# Set-Mile-TOP.net
KiCad netlist of a schematic drawn in EAGLE
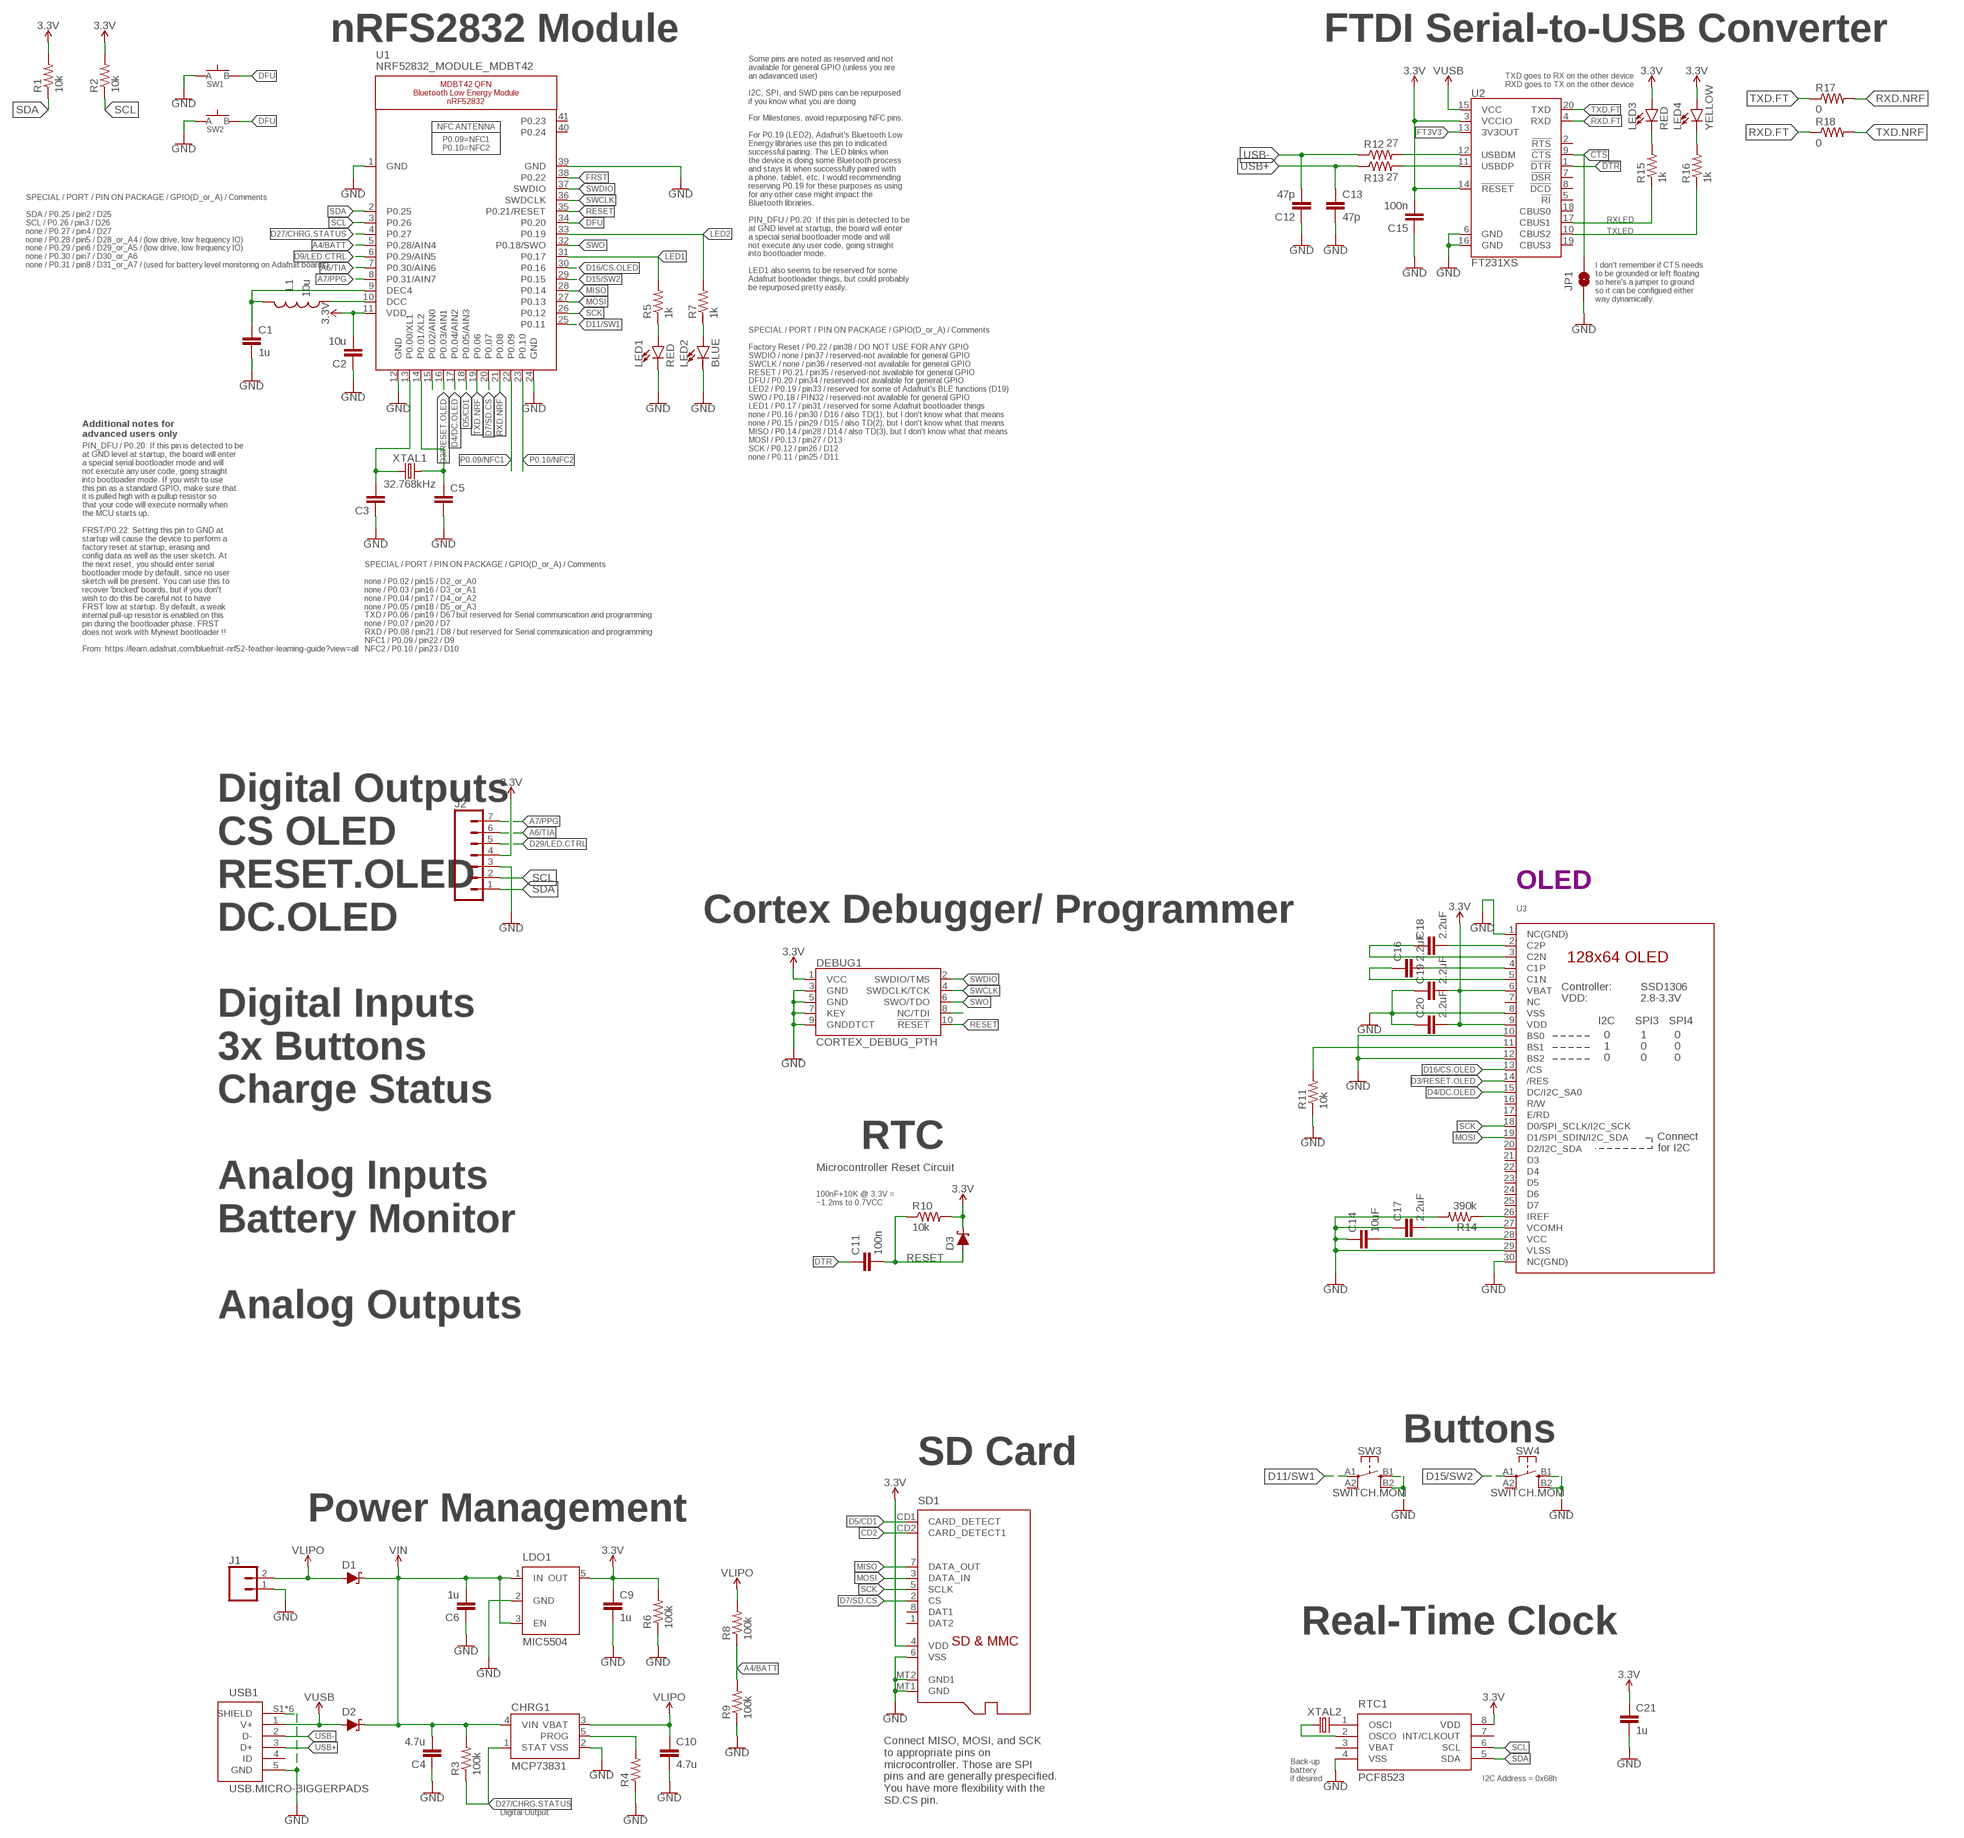
[diagram p0: schematic, sheet 1]

(export (version "E")
  (design (tool "Eeschema 10.0.6"))
  (components
    (comp (ref "C1")
      (value "1u")
      (footprint "eagle-import:C0603")
      (libsource (lib "eagle-import") (part "CAPACITOR0603"))
    )
    (comp (ref "C2")
      (value "10u")
      (footprint "eagle-import:C0805")
      (libsource (lib "eagle-import") (part "CAPACITOR0805"))
    )
    (comp (ref "C3")
      (value "CAPACITOR0603")
      (footprint "eagle-import:C0603")
      (libsource (lib "eagle-import") (part "CAPACITOR0603"))
    )
    (comp (ref "C4")
      (value "4.7u")
      (footprint "eagle-import:C0603")
      (libsource (lib "eagle-import") (part "CAPACITOR0603"))
    )
    (comp (ref "C5")
      (value "CAPACITOR0603")
      (footprint "eagle-import:C0603")
      (libsource (lib "eagle-import") (part "CAPACITOR0603"))
    )
    (comp (ref "C6")
      (value "1u")
      (footprint "eagle-import:C0603")
      (libsource (lib "eagle-import") (part "CAPACITOR0603"))
    )
    (comp (ref "C9")
      (value "1u")
      (footprint "eagle-import:C0603")
      (libsource (lib "eagle-import") (part "CAPACITOR0603"))
    )
    (comp (ref "C10")
      (value "4.7u")
      (footprint "eagle-import:C0603")
      (libsource (lib "eagle-import") (part "CAPACITOR0603"))
    )
    (comp (ref "C11")
      (value "100n")
      (footprint "eagle-import:C0603")
      (libsource (lib "eagle-import") (part "CAPACITOR0603"))
    )
    (comp (ref "C12")
      (value "47p")
      (footprint "eagle-import:C0603")
      (libsource (lib "eagle-import") (part "CAPACITOR0603"))
    )
    (comp (ref "C13")
      (value "47p")
      (footprint "eagle-import:C0603")
      (libsource (lib "eagle-import") (part "CAPACITOR0603"))
    )
    (comp (ref "C14")
      (value "10uF")
      (footprint "eagle-import:C0603")
      (libsource (lib "eagle-import") (part "CAPACITOR0603"))
    )
    (comp (ref "C15")
      (value "100n")
      (footprint "eagle-import:C0603")
      (libsource (lib "eagle-import") (part "CAPACITOR0603"))
    )
    (comp (ref "C16")
      (value "2.2uF")
      (footprint "eagle-import:C0402")
      (libsource (lib "eagle-import") (part "CAPACITOR0402"))
    )
    (comp (ref "C17")
      (value "2.2uF")
      (footprint "eagle-import:C0402")
      (libsource (lib "eagle-import") (part "CAPACITOR0402"))
    )
    (comp (ref "C18")
      (value "2.2uF")
      (footprint "eagle-import:C0402")
      (libsource (lib "eagle-import") (part "CAPACITOR0402"))
    )
    (comp (ref "C19")
      (value "2.2uF")
      (footprint "eagle-import:C0402")
      (libsource (lib "eagle-import") (part "CAPACITOR0402"))
    )
    (comp (ref "C20")
      (value "2.2uF")
      (footprint "eagle-import:C0402")
      (libsource (lib "eagle-import") (part "CAPACITOR0402"))
    )
    (comp (ref "C21")
      (value "1u")
      (footprint "eagle-import:C0603")
      (libsource (lib "eagle-import") (part "CAPACITOR0603"))
    )
    (comp (ref "CHRG1")
      (value "MCP73831")
      (footprint "eagle-import:SOT23-5")
      (libsource (lib "eagle-import") (part "MCP73831"))
    )
    (comp (ref "D1")
      (value "SCHOTTKY-USC")
      (footprint "eagle-import:USC")
      (libsource (lib "eagle-import") (part "SCHOTTKY-USC"))
    )
    (comp (ref "D2")
      (value "SCHOTTKY-USC")
      (footprint "eagle-import:USC")
      (libsource (lib "eagle-import") (part "SCHOTTKY-USC"))
    )
    (comp (ref "D3")
      (value "SCHOTTKY-USC")
      (footprint "eagle-import:USC")
      (libsource (lib "eagle-import") (part "SCHOTTKY-USC"))
    )
    (comp (ref "DEBUG1")
      (value "CORTEX_DEBUG_PTH")
      (footprint "eagle-import:2X5-PTH-1.27MM")
      (libsource (lib "eagle-import") (part "CORTEX_DEBUG_PTH"))
    )
    (comp (ref "J1")
      (value "CONN_02")
      (footprint "eagle-import:1X02")
      (libsource (lib "eagle-import") (part "CONN_02"))
    )
    (comp (ref "J2")
      (value "CONN_07-1.27MM")
      (footprint "eagle-import:1X07_1.27MM")
      (libsource (lib "eagle-import") (part "CONN_07-1.27MM"))
    )
    (comp (ref "JP1")
      (value "JUMPER-SMT_2_NO_SILK")
      (footprint "eagle-import:SMT-JUMPER_2_NO_SILK")
      (libsource (lib "eagle-import") (part "JUMPER-SMT_2_NO_SILK"))
    )
    (comp (ref "L1")
      (value "10u")
      (footprint "eagle-import:L0603")
      (libsource (lib "eagle-import") (part "INDUCTOR0603"))
    )
    (comp (ref "LDO1")
      (value "MIC5504")
      (footprint "eagle-import:SOT23-5")
      (libsource (lib "eagle-import") (part "MIC5504"))
    )
    (comp (ref "LED1")
      (value "RED")
      (footprint "eagle-import:LED-0603")
      (libsource (lib "eagle-import") (part "LED0603"))
    )
    (comp (ref "LED2")
      (value "BLUE")
      (footprint "eagle-import:LED-0603")
      (libsource (lib "eagle-import") (part "LED0603"))
    )
    (comp (ref "LED3")
      (value "RED")
      (footprint "eagle-import:LED-0603")
      (libsource (lib "eagle-import") (part "LED0603"))
    )
    (comp (ref "LED4")
      (value "YELLOW")
      (footprint "eagle-import:LED-0603")
      (libsource (lib "eagle-import") (part "LED0603"))
    )
    (comp (ref "R1")
      (value "10k")
      (footprint "eagle-import:R0603")
      (libsource (lib "eagle-import") (part "RESISTOR0603"))
    )
    (comp (ref "R2")
      (value "10k")
      (footprint "eagle-import:R0603")
      (libsource (lib "eagle-import") (part "RESISTOR0603"))
    )
    (comp (ref "R3")
      (value "100k")
      (footprint "eagle-import:R0603")
      (libsource (lib "eagle-import") (part "RESISTOR0603"))
    )
    (comp (ref "R4")
      (value "RESISTOR0603")
      (footprint "eagle-import:R0603")
      (libsource (lib "eagle-import") (part "RESISTOR0603"))
    )
    (comp (ref "R5")
      (value "1k")
      (footprint "eagle-import:R0603")
      (libsource (lib "eagle-import") (part "RESISTOR0603"))
    )
    (comp (ref "R6")
      (value "100k")
      (footprint "eagle-import:R0603")
      (libsource (lib "eagle-import") (part "RESISTOR0603"))
    )
    (comp (ref "R7")
      (value "1k")
      (footprint "eagle-import:R0603")
      (libsource (lib "eagle-import") (part "RESISTOR0603"))
    )
    (comp (ref "R8")
      (value "100k")
      (footprint "eagle-import:R0603")
      (libsource (lib "eagle-import") (part "RESISTOR0603"))
    )
    (comp (ref "R9")
      (value "100k")
      (footprint "eagle-import:R0603")
      (libsource (lib "eagle-import") (part "RESISTOR0603"))
    )
    (comp (ref "R10")
      (value "10k")
      (footprint "eagle-import:R0603")
      (libsource (lib "eagle-import") (part "RESISTOR0603"))
    )
    (comp (ref "R11")
      (value "10k")
      (footprint "eagle-import:R0603")
      (libsource (lib "eagle-import") (part "RESISTOR0603"))
    )
    (comp (ref "R12")
      (value "27")
      (footprint "eagle-import:R0603")
      (libsource (lib "eagle-import") (part "RESISTOR0603"))
    )
    (comp (ref "R13")
      (value "27")
      (footprint "eagle-import:R0603")
      (libsource (lib "eagle-import") (part "RESISTOR0603"))
    )
    (comp (ref "R14")
      (value "390k")
      (footprint "eagle-import:R0603")
      (libsource (lib "eagle-import") (part "RESISTOR0603"))
    )
    (comp (ref "R15")
      (value "1k")
      (footprint "eagle-import:R0603")
      (libsource (lib "eagle-import") (part "RESISTOR0603"))
    )
    (comp (ref "R16")
      (value "1k")
      (footprint "eagle-import:R0603")
      (libsource (lib "eagle-import") (part "RESISTOR0603"))
    )
    (comp (ref "R17")
      (value "0")
      (footprint "eagle-import:R0603")
      (libsource (lib "eagle-import") (part "RESISTOR0603"))
    )
    (comp (ref "R18")
      (value "0")
      (footprint "eagle-import:R0603")
      (libsource (lib "eagle-import") (part "RESISTOR0603"))
    )
    (comp (ref "RTC1")
      (value "PCF8523")
      (footprint "eagle-import:SO8")
      (libsource (lib "eagle-import") (part "PCF8523"))
    )
    (comp (ref "SD1")
      (value "MICROSD")
      (footprint "eagle-import:MICROSD")
      (libsource (lib "eagle-import") (part "MICROSD"))
    )
    (comp (ref "SW1")
      (value "SPST-PTS830GG140-COPY.1-3")
      (footprint "eagle-import:BUTTON-GULLWING")
      (libsource (lib "eagle-import") (part "SPST-PTS830GG140-COPY.1-3"))
    )
    (comp (ref "SW2")
      (value "SPST-PTS830GG140-COPY.1-3")
      (footprint "eagle-import:BUTTON-GULLWING")
      (libsource (lib "eagle-import") (part "SPST-PTS830GG140-COPY.1-3"))
    )
    (comp (ref "SW3")
      (value "SWITCH.MOM")
      (footprint "eagle-import:TACTILE_SWITCH_SMD_6.2MM_TALL")
      (libsource (lib "eagle-import") (part "SWITCH.MOM"))
    )
    (comp (ref "SW4")
      (value "SWITCH.MOM")
      (footprint "eagle-import:TACTILE_SWITCH_SMD_6.2MM_TALL")
      (libsource (lib "eagle-import") (part "SWITCH.MOM"))
    )
    (comp (ref "U1")
      (value "NRF52832_MODULE_MDBT42")
      (footprint "eagle-import:BLE_MODULE_RAYTAC_MDBT42")
      (libsource (lib "eagle-import") (part "NRF52832_MODULE_MDBT42"))
    )
    (comp (ref "U2")
      (value "FT231XS")
      (footprint "eagle-import:SSOP20_L")
      (libsource (lib "eagle-import") (part "FT231XS"))
    )
    (comp (ref "U3")
      (value "DISP_OLED_UG-2864HSWEG01-NO-WRAPAROUND")
      (footprint "eagle-import:UG-2864HSWEG01_0.96IN_NO-WRAPAROUND")
      (libsource (lib "eagle-import") (part "DISP_OLED_UG-2864HSWEG01-NO-WRAPAROUND"))
    )
    (comp (ref "USB1")
      (value "USB.MICRO-BIGGERPADS")
      (footprint "eagle-import:USB-MICRO-01.BIGGERPADS")
      (libsource (lib "eagle-import") (part "USB.MICRO-BIGGERPADS"))
    )
    (comp (ref "XTAL1")
      (value "32.768kHz")
      (footprint "eagle-import:2-SMD.NOLEAD.2.0MMTO1.2MM")
      (libsource (lib "eagle-import") (part "CRYSTALECS-.327-12.5-12-C-TR"))
    )
    (comp (ref "XTAL2")
      (value "32.7680kHz")
      (footprint "eagle-import:2-SMD.NOLEAD.2.0MMTO1.2MM")
      (libsource (lib "eagle-import") (part "CRYSTALECS-.327-12.5-12-C-TR"))
    )
  )
  (nets
    (net (code "1") (name "/RXLED") (class "Default")
      (node (ref "R15") (pin "1") (pinfunction "1_1") (pintype "passive"))
      (node (ref "U2") (pin "17") (pinfunction "CBUS1_17") (pintype "bidirectional"))
    )
    (net (code "2") (name "/TXLED") (class "Default")
      (node (ref "R16") (pin "1") (pinfunction "1_1") (pintype "passive"))
      (node (ref "U2") (pin "10") (pinfunction "CBUS2_10") (pintype "bidirectional"))
    )
    (net (code "3") (name "/~{CTS}") (class "Default")
      (node (ref "JP1") (pin "2") (pinfunction "2_2") (pintype "passive"))
      (node (ref "U2") (pin "9") (pinfunction "~{CTS}_9") (pintype "bidirectional"))
    )
    (net (code "4") (name "/~{DTR}") (class "Default")
      (node (ref "U2") (pin "1") (pinfunction "~{DTR}_1") (pintype "bidirectional"))
    )
    (net (code "5") (name "3.3V") (class "Default")
      (node (ref "C15") (pin "2") (pinfunction "2_2") (pintype "passive"))
      (node (ref "C19") (pin "2") (pinfunction "2_2") (pintype "passive"))
      (node (ref "C2") (pin "2") (pinfunction "2_2") (pintype "passive"))
      (node (ref "C20") (pin "2") (pinfunction "2_2") (pintype "passive"))
      (node (ref "C21") (pin "1") (pinfunction "1_1") (pintype "passive"))
      (node (ref "C9") (pin "1") (pinfunction "1_1") (pintype "passive"))
      (node (ref "D3") (pin "-") (pinfunction "C_-") (pintype "passive"))
      (node (ref "DEBUG1") (pin "1") (pinfunction "VCC_1") (pintype "bidirectional"))
      (node (ref "J2") (pin "4") (pinfunction "4_4") (pintype "passive"))
      (node (ref "LDO1") (pin "5") (pinfunction "OUT_5") (pintype "bidirectional"))
      (node (ref "LED3") (pin "A") (pinfunction "A_A") (pintype "passive"))
      (node (ref "LED4") (pin "A") (pinfunction "A_A") (pintype "passive"))
      (node (ref "R1") (pin "2") (pinfunction "2_2") (pintype "passive"))
      (node (ref "R10") (pin "2") (pinfunction "2_2") (pintype "passive"))
      (node (ref "R2") (pin "2") (pinfunction "2_2") (pintype "passive"))
      (node (ref "R6") (pin "2") (pinfunction "2_2") (pintype "passive"))
      (node (ref "RTC1") (pin "8") (pinfunction "VDD_8") (pintype "bidirectional"))
      (node (ref "SD1") (pin "4") (pinfunction "VDD_4") (pintype "power_in"))
      (node (ref "U1") (pin "11") (pinfunction "VDD_11") (pintype "bidirectional"))
      (node (ref "U2") (pin "14") (pinfunction "~{RESET}_14") (pintype "bidirectional"))
      (node (ref "U2") (pin "3") (pinfunction "VCCIO_3") (pintype "bidirectional"))
      (node (ref "U3") (pin "6") (pinfunction "VBAT_6") (pintype "input"))
      (node (ref "U3") (pin "9") (pinfunction "VDD_9") (pintype "power_in"))
    )
    (net (code "6") (name "A4{slash}BATT") (class "Default")
      (node (ref "R8") (pin "1") (pinfunction "1_1") (pintype "passive"))
      (node (ref "R9") (pin "2") (pinfunction "2_2") (pintype "passive"))
      (node (ref "U1") (pin "5") (pinfunction "P0.28/AIN4_5") (pintype "bidirectional"))
    )
    (net (code "7") (name "A6{slash}TIA") (class "Default")
      (node (ref "J2") (pin "6") (pinfunction "6_6") (pintype "passive"))
      (node (ref "U1") (pin "7") (pinfunction "P0.30/AIN6_7") (pintype "bidirectional"))
    )
    (net (code "8") (name "A7{slash}PPG") (class "Default")
      (node (ref "J2") (pin "7") (pinfunction "7_7") (pintype "passive"))
      (node (ref "U1") (pin "8") (pinfunction "P0.31/AIN7_8") (pintype "bidirectional"))
    )
    (net (code "9") (name "CD2") (class "Default")
      (node (ref "SD1") (pin "CD2") (pinfunction "CARD_DETECT1_CD2") (pintype "passive"))
    )
    (net (code "10") (name "D3{slash}RESET.OLED") (class "Default")
      (node (ref "U1") (pin "16") (pinfunction "P0.03/AIN1_16") (pintype "bidirectional"))
      (node (ref "U3") (pin "14") (pinfunction "/RES_14") (pintype "input"))
    )
    (net (code "11") (name "D4{slash}DC.OLED") (class "Default")
      (node (ref "U1") (pin "15") (pinfunction "P0.02/AIN0_15") (pintype "bidirectional"))
      (node (ref "U1") (pin "17") (pinfunction "P0.04/AIN2_17") (pintype "bidirectional"))
      (node (ref "U3") (pin "15") (pinfunction "DC/I2C_SA0_15") (pintype "input"))
    )
    (net (code "12") (name "D5{slash}CD1") (class "Default")
      (node (ref "SD1") (pin "CD1") (pinfunction "CARD_DETECT_CD1") (pintype "passive"))
      (node (ref "U1") (pin "18") (pinfunction "P0.05/AIN3_18") (pintype "bidirectional"))
    )
    (net (code "13") (name "D7{slash}SD.CS") (class "Default")
      (node (ref "SD1") (pin "2") (pinfunction "CS_2") (pintype "input"))
      (node (ref "U1") (pin "20") (pinfunction "P0.07_20") (pintype "bidirectional"))
    )
    (net (code "14") (name "D9{slash}LED.CTRL") (class "Default")
      (node (ref "U1") (pin "6") (pinfunction "P0.29/AIN5_6") (pintype "bidirectional"))
    )
    (net (code "15") (name "D11{slash}SW1") (class "Default")
      (node (ref "SW3") (pin "A1") (pinfunction "1_A1") (pintype "passive"))
      (node (ref "U1") (pin "25") (pinfunction "P0.11_25") (pintype "bidirectional"))
    )
    (net (code "16") (name "D15{slash}SW2") (class "Default")
      (node (ref "SW4") (pin "A1") (pinfunction "1_A1") (pintype "passive"))
      (node (ref "U1") (pin "29") (pinfunction "P0.15_29") (pintype "bidirectional"))
    )
    (net (code "17") (name "D16{slash}CS.OLED") (class "Default")
      (node (ref "U1") (pin "30") (pinfunction "P0.16_30") (pintype "bidirectional"))
      (node (ref "U3") (pin "13") (pinfunction "/CS_13") (pintype "input"))
    )
    (net (code "18") (name "D27{slash}CHRG.STATUS") (class "Default")
      (node (ref "CHRG1") (pin "1") (pinfunction "STAT_1") (pintype "output"))
      (node (ref "R3") (pin "1") (pinfunction "1_1") (pintype "passive"))
      (node (ref "U1") (pin "4") (pinfunction "P0.27_4") (pintype "bidirectional"))
    )
    (net (code "19") (name "D29{slash}LED.CTRL") (class "Default")
      (node (ref "J2") (pin "5") (pinfunction "5_5") (pintype "passive"))
    )
    (net (code "20") (name "DFU") (class "Default")
      (node (ref "SW1") (pin "3") (pinfunction "B_3") (pintype "bidirectional"))
      (node (ref "SW2") (pin "3") (pinfunction "B_3") (pintype "bidirectional"))
      (node (ref "U1") (pin "34") (pinfunction "P0.20_34") (pintype "bidirectional"))
    )
    (net (code "21") (name "DTR") (class "Default")
      (node (ref "C11") (pin "1") (pinfunction "1_1") (pintype "passive"))
    )
    (net (code "22") (name "FRST") (class "Default")
      (node (ref "U1") (pin "38") (pinfunction "P0.22_38") (pintype "bidirectional"))
    )
    (net (code "23") (name "FT3V3") (class "Default")
      (node (ref "U2") (pin "13") (pinfunction "3V3OUT_13") (pintype "bidirectional"))
    )
    (net (code "24") (name "GND") (class "Default")
      (node (ref "C1") (pin "2") (pinfunction "2_2") (pintype "passive"))
      (node (ref "C10") (pin "2") (pinfunction "2_2") (pintype "passive"))
      (node (ref "C12") (pin "1") (pinfunction "1_1") (pintype "passive"))
      (node (ref "C13") (pin "2") (pinfunction "2_2") (pintype "passive"))
      (node (ref "C14") (pin "1") (pinfunction "1_1") (pintype "passive"))
      (node (ref "C15") (pin "1") (pinfunction "1_1") (pintype "passive"))
      (node (ref "C17") (pin "1") (pinfunction "1_1") (pintype "passive"))
      (node (ref "C19") (pin "1") (pinfunction "1_1") (pintype "passive"))
      (node (ref "C2") (pin "1") (pinfunction "1_1") (pintype "passive"))
      (node (ref "C20") (pin "1") (pinfunction "1_1") (pintype "passive"))
      (node (ref "C21") (pin "2") (pinfunction "2_2") (pintype "passive"))
      (node (ref "C3") (pin "1") (pinfunction "1_1") (pintype "passive"))
      (node (ref "C4") (pin "1") (pinfunction "1_1") (pintype "passive"))
      (node (ref "C5") (pin "2") (pinfunction "2_2") (pintype "passive"))
      (node (ref "C6") (pin "1") (pinfunction "1_1") (pintype "passive"))
      (node (ref "C9") (pin "2") (pinfunction "2_2") (pintype "passive"))
      (node (ref "CHRG1") (pin "2") (pinfunction "VSS_2") (pintype "power_in"))
      (node (ref "DEBUG1") (pin "3") (pinfunction "GND_3") (pintype "bidirectional"))
      (node (ref "DEBUG1") (pin "5") (pinfunction "GND_5") (pintype "bidirectional"))
      (node (ref "DEBUG1") (pin "7") (pinfunction "KEY_7") (pintype "bidirectional"))
      (node (ref "DEBUG1") (pin "9") (pinfunction "GNDDTCT_9") (pintype "bidirectional"))
      (node (ref "J1") (pin "1") (pinfunction "1_1") (pintype "passive"))
      (node (ref "J2") (pin "3") (pinfunction "3_3") (pintype "passive"))
      (node (ref "JP1") (pin "1") (pinfunction "1_1") (pintype "passive"))
      (node (ref "LDO1") (pin "2") (pinfunction "GND_2") (pintype "bidirectional"))
      (node (ref "LED1") (pin "C") (pinfunction "C_C") (pintype "passive"))
      (node (ref "LED2") (pin "C") (pinfunction "C_C") (pintype "passive"))
      (node (ref "R11") (pin "1") (pinfunction "1_1") (pintype "passive"))
      (node (ref "R14") (pin "2") (pinfunction "2_2") (pintype "passive"))
      (node (ref "R4") (pin "1") (pinfunction "1_1") (pintype "passive"))
      (node (ref "R6") (pin "1") (pinfunction "1_1") (pintype "passive"))
      (node (ref "R9") (pin "1") (pinfunction "1_1") (pintype "passive"))
      (node (ref "RTC1") (pin "4") (pinfunction "VSS_4") (pintype "bidirectional"))
      (node (ref "SD1") (pin "6") (pinfunction "VSS_6") (pintype "power_in"))
      (node (ref "SD1") (pin "MT1") (pinfunction "GND_MT1") (pintype "power_in"))
      (node (ref "SD1") (pin "MT2") (pinfunction "GND1_MT2") (pintype "power_in"))
      (node (ref "SW1") (pin "1") (pinfunction "A_1") (pintype "bidirectional"))
      (node (ref "SW2") (pin "1") (pinfunction "A_1") (pintype "bidirectional"))
      (node (ref "SW3") (pin "B1") (pinfunction "3_B1") (pintype "passive"))
      (node (ref "SW3") (pin "B2") (pinfunction "4_B2") (pintype "passive"))
      (node (ref "SW4") (pin "B1") (pinfunction "3_B1") (pintype "passive"))
      (node (ref "SW4") (pin "B2") (pinfunction "4_B2") (pintype "passive"))
      (node (ref "U1") (pin "1") (pinfunction "GND_1") (pintype "bidirectional"))
      (node (ref "U1") (pin "12") (pinfunction "GND_12") (pintype "bidirectional"))
      (node (ref "U1") (pin "24") (pinfunction "GND_24") (pintype "bidirectional"))
      (node (ref "U1") (pin "39") (pinfunction "GND_39") (pintype "bidirectional"))
      (node (ref "U2") (pin "16") (pinfunction "GND_16") (pintype "bidirectional"))
      (node (ref "U2") (pin "6") (pinfunction "GND_6") (pintype "bidirectional"))
      (node (ref "U3") (pin "1") (pinfunction "NC(GND)_1") (pintype "input"))
      (node (ref "U3") (pin "10") (pinfunction "BS0_10") (pintype "input"))
      (node (ref "U3") (pin "12") (pinfunction "BS2_12") (pintype "input"))
      (node (ref "U3") (pin "29") (pinfunction "VLSS_29") (pintype "power_in"))
      (node (ref "U3") (pin "30") (pinfunction "NC(GND)_30") (pintype "input"))
      (node (ref "U3") (pin "8") (pinfunction "VSS_8") (pintype "power_in"))
      (node (ref "USB1") (pin "5") (pinfunction "GND_5") (pintype "bidirectional"))
      (node (ref "USB1") (pin "S1") (pinfunction "SHIELD_S1") (pintype "bidirectional"))
      (node (ref "USB1") (pin "S2") (pinfunction "SHIELD_S2") (pintype "bidirectional"))
      (node (ref "USB1") (pin "S3") (pinfunction "SHIELD_S3") (pintype "bidirectional"))
      (node (ref "USB1") (pin "S4") (pinfunction "SHIELD_S4") (pintype "bidirectional"))
      (node (ref "USB1") (pin "S5") (pinfunction "SHIELD_S5") (pintype "bidirectional"))
      (node (ref "USB1") (pin "S6") (pinfunction "SHIELD_S6") (pintype "bidirectional"))
    )
    (net (code "25") (name "LED1") (class "Default")
      (node (ref "R5") (pin "2") (pinfunction "2_2") (pintype "passive"))
      (node (ref "U1") (pin "31") (pinfunction "P0.17_31") (pintype "bidirectional"))
    )
    (net (code "26") (name "LED2") (class "Default")
      (node (ref "R7") (pin "2") (pinfunction "2_2") (pintype "passive"))
      (node (ref "U1") (pin "33") (pinfunction "P0.19_33") (pintype "bidirectional"))
    )
    (net (code "27") (name "MISO") (class "Default")
      (node (ref "SD1") (pin "7") (pinfunction "DATA_OUT_7") (pintype "output"))
      (node (ref "U1") (pin "28") (pinfunction "P0.14_28") (pintype "bidirectional"))
    )
    (net (code "28") (name "MOSI") (class "Default")
      (node (ref "SD1") (pin "3") (pinfunction "DATA_IN_3") (pintype "input"))
      (node (ref "U1") (pin "27") (pinfunction "P0.13_27") (pintype "bidirectional"))
      (node (ref "U3") (pin "19") (pinfunction "D1/SPI_SDIN/I2C_SDA_19") (pintype "bidirectional"))
    )
    (net (code "29") (name "Net-(CHRG1-PROG)") (class "Default")
      (node (ref "CHRG1") (pin "5") (pinfunction "PROG_5") (pintype "input"))
      (node (ref "R4") (pin "2") (pinfunction "2_2") (pintype "passive"))
    )
    (net (code "30") (name "Net-(LED1-PadA)") (class "Default")
      (node (ref "LED1") (pin "A") (pinfunction "A_A") (pintype "passive"))
      (node (ref "R5") (pin "1") (pinfunction "1_1") (pintype "passive"))
    )
    (net (code "31") (name "Net-(LED2-PadA)") (class "Default")
      (node (ref "LED2") (pin "A") (pinfunction "A_A") (pintype "passive"))
      (node (ref "R7") (pin "1") (pinfunction "1_1") (pintype "passive"))
    )
    (net (code "32") (name "Net-(LED3-PadC)") (class "Default")
      (node (ref "LED3") (pin "C") (pinfunction "C_C") (pintype "passive"))
      (node (ref "R15") (pin "2") (pinfunction "2_2") (pintype "passive"))
    )
    (net (code "33") (name "Net-(LED4-PadC)") (class "Default")
      (node (ref "LED4") (pin "C") (pinfunction "C_C") (pintype "passive"))
      (node (ref "R16") (pin "2") (pinfunction "2_2") (pintype "passive"))
    )
    (net (code "34") (name "Net-(RTC1-OSCI)") (class "Default")
      (node (ref "RTC1") (pin "1") (pinfunction "OSCI_1") (pintype "bidirectional"))
      (node (ref "XTAL2") (pin "P$2") (pinfunction "2_P$2") (pintype "passive"))
    )
    (net (code "35") (name "Net-(RTC1-OSCO)") (class "Default")
      (node (ref "RTC1") (pin "2") (pinfunction "OSCO_2") (pintype "bidirectional"))
      (node (ref "XTAL2") (pin "P$1") (pinfunction "1_P$1") (pintype "passive"))
    )
    (net (code "36") (name "Net-(U1-DCC)") (class "Default")
      (node (ref "L1") (pin "1") (pinfunction "1_1") (pintype "passive"))
      (node (ref "U1") (pin "10") (pinfunction "DCC_10") (pintype "bidirectional"))
    )
    (net (code "37") (name "Net-(U1-DEC4)") (class "Default")
      (node (ref "C1") (pin "1") (pinfunction "1_1") (pintype "passive"))
      (node (ref "L1") (pin "2") (pinfunction "2_2") (pintype "passive"))
      (node (ref "U1") (pin "9") (pinfunction "DEC4_9") (pintype "bidirectional"))
    )
    (net (code "38") (name "Net-(U1-P0.00{slash}XL1)") (class "Default")
      (node (ref "C3") (pin "2") (pinfunction "2_2") (pintype "passive"))
      (node (ref "U1") (pin "13") (pinfunction "P0.00/XL1_13") (pintype "bidirectional"))
      (node (ref "XTAL1") (pin "P$1") (pinfunction "1_P$1") (pintype "passive"))
    )
    (net (code "39") (name "Net-(U1-P0.01{slash}XL2)") (class "Default")
      (node (ref "C5") (pin "1") (pinfunction "1_1") (pintype "passive"))
      (node (ref "U1") (pin "14") (pinfunction "P0.01/XL2_14") (pintype "bidirectional"))
      (node (ref "XTAL1") (pin "P$2") (pinfunction "2_P$2") (pintype "passive"))
    )
    (net (code "40") (name "Net-(U2-USBDM)") (class "Default")
      (node (ref "R12") (pin "2") (pinfunction "2_2") (pintype "passive"))
      (node (ref "U2") (pin "12") (pinfunction "USBDM_12") (pintype "bidirectional"))
    )
    (net (code "41") (name "Net-(U2-USBDP)") (class "Default")
      (node (ref "R13") (pin "2") (pinfunction "2_2") (pintype "passive"))
      (node (ref "U2") (pin "11") (pinfunction "USBDP_11") (pintype "bidirectional"))
    )
    (net (code "42") (name "Net-(U3-BS1)") (class "Default")
      (node (ref "R11") (pin "2") (pinfunction "2_2") (pintype "passive"))
      (node (ref "U3") (pin "11") (pinfunction "BS1_11") (pintype "input"))
    )
    (net (code "43") (name "Net-(U3-C1N)") (class "Default")
      (node (ref "C16") (pin "1") (pinfunction "1_1") (pintype "passive"))
      (node (ref "U3") (pin "5") (pinfunction "C1N_5") (pintype "input"))
    )
    (net (code "44") (name "Net-(U3-C1P)") (class "Default")
      (node (ref "C16") (pin "2") (pinfunction "2_2") (pintype "passive"))
      (node (ref "U3") (pin "4") (pinfunction "C1P_4") (pintype "input"))
    )
    (net (code "45") (name "Net-(U3-C2N)") (class "Default")
      (node (ref "C18") (pin "1") (pinfunction "1_1") (pintype "passive"))
      (node (ref "U3") (pin "3") (pinfunction "C2N_3") (pintype "input"))
    )
    (net (code "46") (name "Net-(U3-C2P)") (class "Default")
      (node (ref "C18") (pin "2") (pinfunction "2_2") (pintype "passive"))
      (node (ref "U3") (pin "2") (pinfunction "C2P_2") (pintype "input"))
    )
    (net (code "47") (name "Net-(U3-IREF)") (class "Default")
      (node (ref "R14") (pin "1") (pinfunction "1_1") (pintype "passive"))
      (node (ref "U3") (pin "26") (pinfunction "IREF_26") (pintype "input"))
    )
    (net (code "48") (name "Net-(U3-VCC)") (class "Default")
      (node (ref "C14") (pin "2") (pinfunction "2_2") (pintype "passive"))
      (node (ref "U3") (pin "28") (pinfunction "VCC_28") (pintype "power_in"))
    )
    (net (code "49") (name "Net-(U3-VCOMH)") (class "Default")
      (node (ref "C17") (pin "2") (pinfunction "2_2") (pintype "passive"))
      (node (ref "U3") (pin "27") (pinfunction "VCOMH_27") (pintype "output"))
    )
    (net (code "50") (name "P0.09{slash}NFC1") (class "Default")
      (node (ref "U1") (pin "22") (pinfunction "P0.09_22") (pintype "bidirectional"))
    )
    (net (code "51") (name "P0.10{slash}NFC2") (class "Default")
      (node (ref "U1") (pin "23") (pinfunction "P0.10_23") (pintype "bidirectional"))
    )
    (net (code "52") (name "RESET") (class "Default")
      (node (ref "C11") (pin "2") (pinfunction "2_2") (pintype "passive"))
      (node (ref "D3") (pin "+") (pinfunction "A_+") (pintype "passive"))
      (node (ref "DEBUG1") (pin "10") (pinfunction "~{RESET}_10") (pintype "bidirectional"))
      (node (ref "R10") (pin "1") (pinfunction "1_1") (pintype "passive"))
      (node (ref "U1") (pin "35") (pinfunction "P0.21/RESET_35") (pintype "bidirectional"))
    )
    (net (code "53") (name "RXD.FT") (class "Default")
      (node (ref "R18") (pin "1") (pinfunction "1_1") (pintype "passive"))
      (node (ref "U2") (pin "4") (pinfunction "RXD_4") (pintype "bidirectional"))
    )
    (net (code "54") (name "RXD.NRF") (class "Default")
      (node (ref "R17") (pin "2") (pinfunction "2_2") (pintype "passive"))
      (node (ref "U1") (pin "21") (pinfunction "P0.08_21") (pintype "bidirectional"))
    )
    (net (code "55") (name "SCK") (class "Default")
      (node (ref "SD1") (pin "5") (pinfunction "SCLK_5") (pintype "input"))
      (node (ref "U1") (pin "26") (pinfunction "P0.12_26") (pintype "bidirectional"))
      (node (ref "U3") (pin "18") (pinfunction "D0/SPI_SCLK/I2C_SCK_18") (pintype "bidirectional"))
    )
    (net (code "56") (name "SCL") (class "Default")
      (node (ref "J2") (pin "2") (pinfunction "2_2") (pintype "passive"))
      (node (ref "R2") (pin "1") (pinfunction "1_1") (pintype "passive"))
      (node (ref "RTC1") (pin "6") (pinfunction "SCL_6") (pintype "bidirectional"))
      (node (ref "U1") (pin "3") (pinfunction "P0.26_3") (pintype "bidirectional"))
    )
    (net (code "57") (name "SDA") (class "Default")
      (node (ref "J2") (pin "1") (pinfunction "1_1") (pintype "passive"))
      (node (ref "R1") (pin "1") (pinfunction "1_1") (pintype "passive"))
      (node (ref "RTC1") (pin "5") (pinfunction "SDA_5") (pintype "bidirectional"))
      (node (ref "U1") (pin "2") (pinfunction "P0.25_2") (pintype "bidirectional"))
    )
    (net (code "58") (name "SWCLK") (class "Default")
      (node (ref "DEBUG1") (pin "4") (pinfunction "SWDCLK/TCK_4") (pintype "bidirectional"))
      (node (ref "U1") (pin "36") (pinfunction "SWDCLK_36") (pintype "bidirectional"))
    )
    (net (code "59") (name "SWDIO") (class "Default")
      (node (ref "DEBUG1") (pin "2") (pinfunction "SWDIO/TMS_2") (pintype "bidirectional"))
      (node (ref "U1") (pin "37") (pinfunction "SWDIO_37") (pintype "bidirectional"))
    )
    (net (code "60") (name "SWO") (class "Default")
      (node (ref "DEBUG1") (pin "6") (pinfunction "SWO/TDO_6") (pintype "bidirectional"))
      (node (ref "U1") (pin "32") (pinfunction "P0.18/SWO_32") (pintype "bidirectional"))
    )
    (net (code "61") (name "TXD.FT") (class "Default")
      (node (ref "R17") (pin "1") (pinfunction "1_1") (pintype "passive"))
      (node (ref "U2") (pin "20") (pinfunction "TXD_20") (pintype "bidirectional"))
    )
    (net (code "62") (name "TXD.NRF") (class "Default")
      (node (ref "R18") (pin "2") (pinfunction "2_2") (pintype "passive"))
      (node (ref "U1") (pin "19") (pinfunction "P0.06_19") (pintype "bidirectional"))
    )
    (net (code "63") (name "USB+") (class "Default")
      (node (ref "C13") (pin "1") (pinfunction "1_1") (pintype "passive"))
      (node (ref "R13") (pin "1") (pinfunction "1_1") (pintype "passive"))
      (node (ref "USB1") (pin "3") (pinfunction "D+_3") (pintype "bidirectional"))
    )
    (net (code "64") (name "USB-") (class "Default")
      (node (ref "C12") (pin "2") (pinfunction "2_2") (pintype "passive"))
      (node (ref "R12") (pin "1") (pinfunction "1_1") (pintype "passive"))
      (node (ref "USB1") (pin "2") (pinfunction "D-_2") (pintype "bidirectional"))
    )
    (net (code "65") (name "VIN") (class "Default")
      (node (ref "C4") (pin "2") (pinfunction "2_2") (pintype "passive"))
      (node (ref "C6") (pin "2") (pinfunction "2_2") (pintype "passive"))
      (node (ref "CHRG1") (pin "4") (pinfunction "VIN_4") (pintype "power_in"))
      (node (ref "D1") (pin "-") (pinfunction "C_-") (pintype "passive"))
      (node (ref "D2") (pin "-") (pinfunction "C_-") (pintype "passive"))
      (node (ref "LDO1") (pin "1") (pinfunction "IN_1") (pintype "bidirectional"))
      (node (ref "LDO1") (pin "3") (pinfunction "EN_3") (pintype "bidirectional"))
      (node (ref "R3") (pin "2") (pinfunction "2_2") (pintype "passive"))
    )
    (net (code "66") (name "VLIPO") (class "Default")
      (node (ref "C10") (pin "1") (pinfunction "1_1") (pintype "passive"))
      (node (ref "CHRG1") (pin "3") (pinfunction "VBAT_3") (pintype "power_in"))
      (node (ref "D1") (pin "+") (pinfunction "A_+") (pintype "passive"))
      (node (ref "J1") (pin "2") (pinfunction "2_2") (pintype "passive"))
      (node (ref "R8") (pin "2") (pinfunction "2_2") (pintype "passive"))
    )
    (net (code "67") (name "VUSB") (class "Default")
      (node (ref "D2") (pin "+") (pinfunction "A_+") (pintype "passive"))
      (node (ref "U2") (pin "15") (pinfunction "VCC_15") (pintype "bidirectional"))
      (node (ref "USB1") (pin "1") (pinfunction "V+_1") (pintype "bidirectional"))
    )
    (net (code "68") (name "unconnected-(DEBUG1-NC{slash}TDI-Pad8)") (class "Default")
      (node (ref "DEBUG1") (pin "8") (pinfunction "NC/TDI_8") (pintype "bidirectional"))
    )
    (net (code "69") (name "unconnected-(RTC1-INT{slash}CLKOUT-Pad7)") (class "Default")
      (node (ref "RTC1") (pin "7") (pinfunction "INT/CLKOUT_7") (pintype "bidirectional"))
    )
    (net (code "70") (name "unconnected-(RTC1-VBAT-Pad3)") (class "Default")
      (node (ref "RTC1") (pin "3") (pinfunction "VBAT_3") (pintype "bidirectional"))
    )
    (net (code "71") (name "unconnected-(SD1-DAT1-Pad8)") (class "Default")
      (node (ref "SD1") (pin "8") (pinfunction "DAT1_8") (pintype "bidirectional"))
    )
    (net (code "72") (name "unconnected-(SD1-DAT2-Pad1)") (class "Default")
      (node (ref "SD1") (pin "1") (pinfunction "DAT2_1") (pintype "bidirectional"))
    )
    (net (code "73") (name "unconnected-(SW3-2-PadA2)") (class "Default")
      (node (ref "SW3") (pin "A2") (pinfunction "2_A2") (pintype "passive"))
    )
    (net (code "74") (name "unconnected-(SW4-2-PadA2)") (class "Default")
      (node (ref "SW4") (pin "A2") (pinfunction "2_A2") (pintype "passive"))
    )
    (net (code "75") (name "unconnected-(U1-P0.23-Pad41)") (class "Default")
      (node (ref "U1") (pin "41") (pinfunction "P0.23_41") (pintype "bidirectional"))
    )
    (net (code "76") (name "unconnected-(U1-P0.24-Pad40)") (class "Default")
      (node (ref "U1") (pin "40") (pinfunction "P0.24_40") (pintype "bidirectional"))
    )
    (net (code "77") (name "unconnected-(U2-CBUS0-Pad18)") (class "Default")
      (node (ref "U2") (pin "18") (pinfunction "CBUS0_18") (pintype "bidirectional"))
    )
    (net (code "78") (name "unconnected-(U2-CBUS3-Pad19)") (class "Default")
      (node (ref "U2") (pin "19") (pinfunction "CBUS3_19") (pintype "bidirectional"))
    )
    (net (code "79") (name "unconnected-(U2-~{DCD}-Pad8)") (class "Default")
      (node (ref "U2") (pin "8") (pinfunction "~{DCD}_8") (pintype "bidirectional"))
    )
    (net (code "80") (name "unconnected-(U2-~{DSR}-Pad7)") (class "Default")
      (node (ref "U2") (pin "7") (pinfunction "~{DSR}_7") (pintype "bidirectional"))
    )
    (net (code "81") (name "unconnected-(U2-~{RI}-Pad5)") (class "Default")
      (node (ref "U2") (pin "5") (pinfunction "~{RI}_5") (pintype "bidirectional"))
    )
    (net (code "82") (name "unconnected-(U2-~{RTS}-Pad2)") (class "Default")
      (node (ref "U2") (pin "2") (pinfunction "~{RTS}_2") (pintype "bidirectional"))
    )
    (net (code "83") (name "unconnected-(U3-D2{slash}I2C_SDA-Pad20)") (class "Default")
      (node (ref "U3") (pin "20") (pinfunction "D2/I2C_SDA_20") (pintype "bidirectional"))
    )
    (net (code "84") (name "unconnected-(U3-D3-Pad21)") (class "Default")
      (node (ref "U3") (pin "21") (pinfunction "D3_21") (pintype "bidirectional"))
    )
    (net (code "85") (name "unconnected-(U3-D4-Pad22)") (class "Default")
      (node (ref "U3") (pin "22") (pinfunction "D4_22") (pintype "bidirectional"))
    )
    (net (code "86") (name "unconnected-(U3-D5-Pad23)") (class "Default")
      (node (ref "U3") (pin "23") (pinfunction "D5_23") (pintype "bidirectional"))
    )
    (net (code "87") (name "unconnected-(U3-D6-Pad24)") (class "Default")
      (node (ref "U3") (pin "24") (pinfunction "D6_24") (pintype "bidirectional"))
    )
    (net (code "88") (name "unconnected-(U3-D7-Pad25)") (class "Default")
      (node (ref "U3") (pin "25") (pinfunction "D7_25") (pintype "bidirectional"))
    )
    (net (code "89") (name "unconnected-(U3-E{slash}RD-Pad17)") (class "Default")
      (node (ref "U3") (pin "17") (pinfunction "E/RD_17") (pintype "input"))
    )
    (net (code "90") (name "unconnected-(U3-NC-Pad7)") (class "Default")
      (node (ref "U3") (pin "7") (pinfunction "NC_7") (pintype "no_connect"))
    )
    (net (code "91") (name "unconnected-(U3-R{slash}W-Pad16)") (class "Default")
      (node (ref "U3") (pin "16") (pinfunction "R/W_16") (pintype "input"))
    )
    (net (code "92") (name "unconnected-(USB1-ID-Pad4)") (class "Default")
      (node (ref "USB1") (pin "4") (pinfunction "ID_4") (pintype "bidirectional"))
    )
  )
)
